# bbot.net
KiCad netlist of a schematic drawn in EAGLE
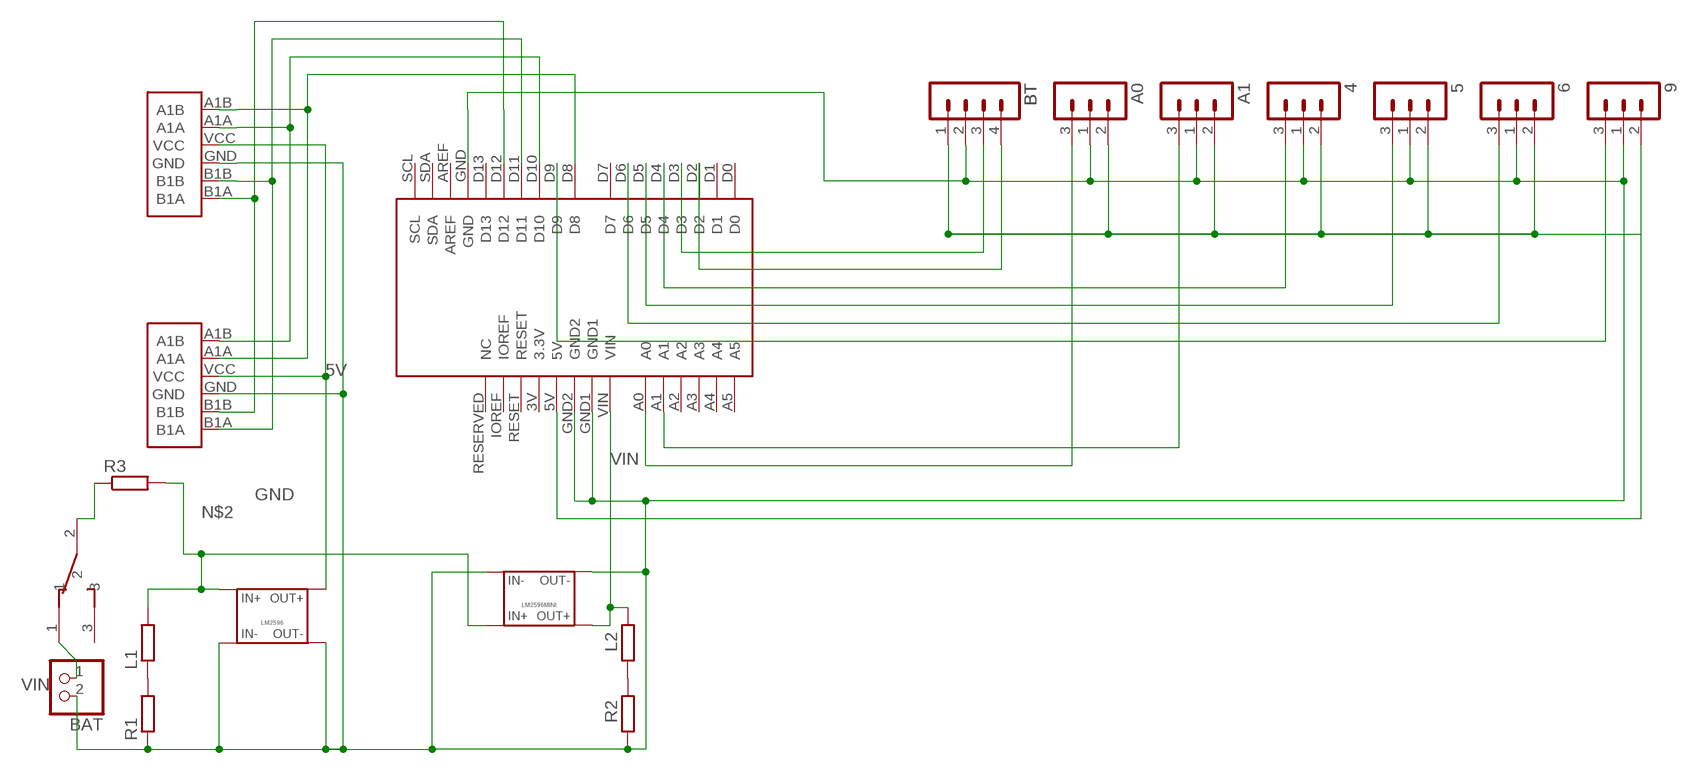
[diagram p0: schematic, sheet 1]

(export (version "E")
  (design (tool "Eeschema 10.0.6"))
  (components
    (comp (ref "4")
      (value "BB-PIN3")
      (footprint "eagle-import:BB-PIN3")
      (libsource (lib "eagle-import") (part "BB-PIN3"))
    )
    (comp (ref "5")
      (value "BB-PIN3")
      (footprint "eagle-import:BB-PIN3")
      (libsource (lib "eagle-import") (part "BB-PIN3"))
    )
    (comp (ref "6")
      (value "BB-PIN3")
      (footprint "eagle-import:BB-PIN3")
      (libsource (lib "eagle-import") (part "BB-PIN3"))
    )
    (comp (ref "9")
      (value "BB-PIN3")
      (footprint "eagle-import:BB-PIN3")
      (libsource (lib "eagle-import") (part "BB-PIN3"))
    )
    (comp (ref "A0")
      (value "BB-PIN3")
      (footprint "eagle-import:BB-PIN3")
      (libsource (lib "eagle-import") (part "BB-PIN3"))
    )
    (comp (ref "A1")
      (value "BB-PIN3")
      (footprint "eagle-import:BB-PIN3")
      (libsource (lib "eagle-import") (part "BB-PIN3"))
    )
    (comp (ref "BAT")
      (value "VIN")
      (footprint "eagle-import:JST-PH-2-THM")
      (libsource (lib "eagle-import") (part "JST_2PIN-THM"))
    )
    (comp (ref "BT")
      (value "BB-HC06")
      (footprint "eagle-import:BB-HC06")
      (libsource (lib "eagle-import") (part "BB-HC06"))
    )
    (comp (ref "L1")
      (value "BB-RESM0805")
      (footprint "eagle-import:M0805")
      (libsource (lib "eagle-import") (part "BB-RESM0805"))
    )
    (comp (ref "L2")
      (value "BB-RESM0805")
      (footprint "eagle-import:M0805")
      (libsource (lib "eagle-import") (part "BB-RESM0805"))
    )
    (comp (ref "LM2596")
      (value "BB-LM2596")
      (footprint "eagle-import:BB-LM2596")
      (fields (field (name "SIZE") "LM2596"))
      (libsource (lib "eagle-import") (part "BB-LM2596"))
    )
    (comp (ref "LM2596MINI")
      (value "BB-LM2596MINI")
      (footprint "eagle-import:BB-LM2596MINI")
      (libsource (lib "eagle-import") (part "BB-LM2596MINI"))
    )
    (comp (ref "R1")
      (value "BB-RESM0805")
      (footprint "eagle-import:M0805")
      (libsource (lib "eagle-import") (part "BB-RESM0805"))
    )
    (comp (ref "R2")
      (value "BB-RESM0805")
      (footprint "eagle-import:M0805")
      (libsource (lib "eagle-import") (part "BB-RESM0805"))
    )
    (comp (ref "R3")
      (value "R-EU_0207/5V")
      (footprint "eagle-import:0207_5V")
      (libsource (lib "eagle-import") (part "R-EU_0207/5V"))
    )
    (comp (ref "SW1")
      (value "BB-SWITCHBB-SW")
      (footprint "eagle-import:BB-SWITCH")
      (libsource (lib "eagle-import") (part "BB-SWITCHBB-SW"))
    )
    (comp (ref "U$1")
      (value "BB-ARD")
      (footprint "eagle-import:BB-ARD")
      (libsource (lib "eagle-import") (part "BB-ARD"))
    )
    (comp (ref "U$2")
      (value "BB-PTEH")
      (footprint "eagle-import:BB-PTEH")
      (libsource (lib "eagle-import") (part "BB-PTEH"))
    )
    (comp (ref "U$3")
      (value "BB-PTEH")
      (footprint "eagle-import:BB-PTEH")
      (libsource (lib "eagle-import") (part "BB-PTEH"))
    )
  )
  (nets
    (net (code "1") (name "/5V") (class "Default")
      (node (ref "LM2596") (pin "OUT+") (pinfunction "OUT+_OUT+") (pintype "bidirectional"))
      (node (ref "U$2") (pin "VCC") (pinfunction "VCC_VCC") (pintype "bidirectional"))
      (node (ref "U$3") (pin "VCC") (pinfunction "VCC_VCC") (pintype "bidirectional"))
    )
    (net (code "2") (name "/GND") (class "Default")
      (node (ref "4") (pin "1") (pinfunction "GND_1") (pintype "passive"))
      (node (ref "5") (pin "1") (pinfunction "GND_1") (pintype "passive"))
      (node (ref "6") (pin "1") (pinfunction "GND_1") (pintype "passive"))
      (node (ref "9") (pin "1") (pinfunction "GND_1") (pintype "passive"))
      (node (ref "A0") (pin "1") (pinfunction "GND_1") (pintype "passive"))
      (node (ref "A1") (pin "1") (pinfunction "GND_1") (pintype "passive"))
      (node (ref "BAT") (pin "2") (pinfunction "1_2") (pintype "passive"))
      (node (ref "BT") (pin "2") (pinfunction "2_2") (pintype "passive"))
      (node (ref "LM2596") (pin "IN-") (pinfunction "IN-_IN-") (pintype "bidirectional"))
      (node (ref "LM2596") (pin "OUT-") (pinfunction "OUT-_OUT-") (pintype "bidirectional"))
      (node (ref "LM2596MINI") (pin "IN-") (pinfunction "IN-_IN-") (pintype "bidirectional"))
      (node (ref "LM2596MINI") (pin "OUT-") (pinfunction "OUT-_OUT-") (pintype "bidirectional"))
      (node (ref "R1") (pin "1") (pinfunction "1_1") (pintype "passive"))
      (node (ref "R2") (pin "1") (pinfunction "1_1") (pintype "passive"))
      (node (ref "U$1") (pin "GND") (pinfunction "GND_GND") (pintype "bidirectional"))
      (node (ref "U$1") (pin "GND1") (pinfunction "GND1_GND1") (pintype "bidirectional"))
      (node (ref "U$1") (pin "GND2") (pinfunction "GND2_GND2") (pintype "bidirectional"))
      (node (ref "U$2") (pin "GND") (pinfunction "GND_GND") (pintype "bidirectional"))
      (node (ref "U$3") (pin "GND") (pinfunction "GND_GND") (pintype "bidirectional"))
    )
    (net (code "3") (name "/N$2") (class "Default")
      (node (ref "R3") (pin "1") (pinfunction "1_1") (pintype "passive"))
      (node (ref "SW1") (pin "2") (pinfunction "2_2") (pintype "bidirectional"))
    )
    (net (code "4") (name "/VIN") (class "Default")
      (node (ref "L2") (pin "2") (pinfunction "2_2") (pintype "passive"))
      (node (ref "LM2596MINI") (pin "OUT+") (pinfunction "OUT+_OUT+") (pintype "bidirectional"))
      (node (ref "U$1") (pin "VIN") (pinfunction "VIN_VIN") (pintype "bidirectional"))
    )
    (net (code "5") (name "Net-(4-5V)") (class "Default")
      (node (ref "4") (pin "2") (pinfunction "5V_2") (pintype "passive"))
      (node (ref "5") (pin "2") (pinfunction "5V_2") (pintype "passive"))
      (node (ref "6") (pin "2") (pinfunction "5V_2") (pintype "passive"))
      (node (ref "9") (pin "2") (pinfunction "5V_2") (pintype "passive"))
      (node (ref "A0") (pin "2") (pinfunction "5V_2") (pintype "passive"))
      (node (ref "A1") (pin "2") (pinfunction "5V_2") (pintype "passive"))
      (node (ref "BT") (pin "1") (pinfunction "1_1") (pintype "passive"))
      (node (ref "U$1") (pin "5V") (pinfunction "5V_5V") (pintype "bidirectional"))
    )
    (net (code "6") (name "Net-(4-S)") (class "Default")
      (node (ref "4") (pin "3") (pinfunction "S_3") (pintype "passive"))
      (node (ref "U$1") (pin "D4") (pinfunction "D4_D4") (pintype "bidirectional"))
    )
    (net (code "7") (name "Net-(5-S)") (class "Default")
      (node (ref "5") (pin "3") (pinfunction "S_3") (pintype "passive"))
      (node (ref "U$1") (pin "D5") (pinfunction "D5_D5") (pintype "bidirectional"))
    )
    (net (code "8") (name "Net-(6-S)") (class "Default")
      (node (ref "6") (pin "3") (pinfunction "S_3") (pintype "passive"))
      (node (ref "U$1") (pin "D6") (pinfunction "D6_D6") (pintype "bidirectional"))
    )
    (net (code "9") (name "Net-(9-S)") (class "Default")
      (node (ref "9") (pin "3") (pinfunction "S_3") (pintype "passive"))
      (node (ref "U$1") (pin "D9") (pinfunction "D9_D9") (pintype "bidirectional"))
    )
    (net (code "10") (name "Net-(A0-S)") (class "Default")
      (node (ref "A0") (pin "3") (pinfunction "S_3") (pintype "passive"))
      (node (ref "U$1") (pin "A0") (pinfunction "A0_A0") (pintype "bidirectional"))
    )
    (net (code "11") (name "Net-(A1-S)") (class "Default")
      (node (ref "A1") (pin "3") (pinfunction "S_3") (pintype "passive"))
      (node (ref "U$1") (pin "A1") (pinfunction "A1_A1") (pintype "bidirectional"))
    )
    (net (code "12") (name "Net-(BAT-2)") (class "Default")
      (node (ref "BAT") (pin "1") (pinfunction "2_1") (pintype "passive"))
      (node (ref "SW1") (pin "1") (pinfunction "1_1") (pintype "bidirectional"))
    )
    (net (code "13") (name "Net-(BT-Pad3)") (class "Default")
      (node (ref "BT") (pin "3") (pinfunction "3_3") (pintype "passive"))
      (node (ref "U$1") (pin "D3") (pinfunction "D3_D3") (pintype "bidirectional"))
    )
    (net (code "14") (name "Net-(BT-Pad4)") (class "Default")
      (node (ref "BT") (pin "4") (pinfunction "4_4") (pintype "passive"))
      (node (ref "U$1") (pin "D2") (pinfunction "D2_D2") (pintype "bidirectional"))
    )
    (net (code "15") (name "Net-(L1-Pad1)") (class "Default")
      (node (ref "L1") (pin "1") (pinfunction "1_1") (pintype "passive"))
      (node (ref "R1") (pin "2") (pinfunction "2_2") (pintype "passive"))
    )
    (net (code "16") (name "Net-(L1-Pad2)") (class "Default")
      (node (ref "L1") (pin "2") (pinfunction "2_2") (pintype "passive"))
      (node (ref "LM2596") (pin "IN+") (pinfunction "IN+_IN+") (pintype "bidirectional"))
      (node (ref "LM2596MINI") (pin "IN+") (pinfunction "IN+_IN+") (pintype "bidirectional"))
      (node (ref "R3") (pin "2") (pinfunction "2_2") (pintype "passive"))
    )
    (net (code "17") (name "Net-(L2-Pad1)") (class "Default")
      (node (ref "L2") (pin "1") (pinfunction "1_1") (pintype "passive"))
      (node (ref "R2") (pin "2") (pinfunction "2_2") (pintype "passive"))
    )
    (net (code "18") (name "Net-(U$1-PadD8)") (class "Default")
      (node (ref "U$1") (pin "D8") (pinfunction "D8_D8") (pintype "bidirectional"))
      (node (ref "U$2") (pin "A1B") (pinfunction "A1B_A1B") (pintype "bidirectional"))
      (node (ref "U$3") (pin "A1A") (pinfunction "A1A_A1A") (pintype "bidirectional"))
    )
    (net (code "19") (name "Net-(U$1-PadD10)") (class "Default")
      (node (ref "U$1") (pin "D10") (pinfunction "D10_D10") (pintype "bidirectional"))
      (node (ref "U$2") (pin "A1A") (pinfunction "A1A_A1A") (pintype "bidirectional"))
      (node (ref "U$3") (pin "A1B") (pinfunction "A1B_A1B") (pintype "bidirectional"))
    )
    (net (code "20") (name "Net-(U$1-PadD11)") (class "Default")
      (node (ref "U$1") (pin "D11") (pinfunction "D11_D11") (pintype "bidirectional"))
      (node (ref "U$2") (pin "B1B") (pinfunction "B1B_B1B") (pintype "bidirectional"))
      (node (ref "U$3") (pin "B1A") (pinfunction "B1A_B1A") (pintype "bidirectional"))
    )
    (net (code "21") (name "Net-(U$1-PadD12)") (class "Default")
      (node (ref "U$1") (pin "D12") (pinfunction "D12_D12") (pintype "bidirectional"))
      (node (ref "U$2") (pin "B1A") (pinfunction "B1A_B1A") (pintype "bidirectional"))
      (node (ref "U$3") (pin "B1B") (pinfunction "B1B_B1B") (pintype "bidirectional"))
    )
    (net (code "22") (name "unconnected-(SW1-Pad3)") (class "Default")
      (node (ref "SW1") (pin "3") (pinfunction "3_3") (pintype "bidirectional"))
    )
    (net (code "23") (name "unconnected-(U$1-3.3V-Pad3V)") (class "Default")
      (node (ref "U$1") (pin "3V") (pinfunction "3.3V_3V") (pintype "bidirectional"))
    )
    (net (code "24") (name "unconnected-(U$1-NC-PadRESERVED)") (class "Default")
      (node (ref "U$1") (pin "RESERVED") (pinfunction "NC_RESERVED") (pintype "bidirectional"))
    )
    (net (code "25") (name "unconnected-(U$1-PadA2)") (class "Default")
      (node (ref "U$1") (pin "A2") (pinfunction "A2_A2") (pintype "bidirectional"))
    )
    (net (code "26") (name "unconnected-(U$1-PadA3)") (class "Default")
      (node (ref "U$1") (pin "A3") (pinfunction "A3_A3") (pintype "bidirectional"))
    )
    (net (code "27") (name "unconnected-(U$1-PadA4)") (class "Default")
      (node (ref "U$1") (pin "A4") (pinfunction "A4_A4") (pintype "bidirectional"))
    )
    (net (code "28") (name "unconnected-(U$1-PadA5)") (class "Default")
      (node (ref "U$1") (pin "A5") (pinfunction "A5_A5") (pintype "bidirectional"))
    )
    (net (code "29") (name "unconnected-(U$1-PadAREF)") (class "Default")
      (node (ref "U$1") (pin "AREF") (pinfunction "AREF_AREF") (pintype "bidirectional"))
    )
    (net (code "30") (name "unconnected-(U$1-PadD0)") (class "Default")
      (node (ref "U$1") (pin "D0") (pinfunction "D0_D0") (pintype "bidirectional"))
    )
    (net (code "31") (name "unconnected-(U$1-PadD1)") (class "Default")
      (node (ref "U$1") (pin "D1") (pinfunction "D1_D1") (pintype "bidirectional"))
    )
    (net (code "32") (name "unconnected-(U$1-PadD7)") (class "Default")
      (node (ref "U$1") (pin "D7") (pinfunction "D7_D7") (pintype "bidirectional"))
    )
    (net (code "33") (name "unconnected-(U$1-PadD13)") (class "Default")
      (node (ref "U$1") (pin "D13") (pinfunction "D13_D13") (pintype "bidirectional"))
    )
    (net (code "34") (name "unconnected-(U$1-PadIOREF)") (class "Default")
      (node (ref "U$1") (pin "IOREF") (pinfunction "IOREF_IOREF") (pintype "bidirectional"))
    )
    (net (code "35") (name "unconnected-(U$1-PadRESET)") (class "Default")
      (node (ref "U$1") (pin "RESET") (pinfunction "RESET_RESET") (pintype "bidirectional"))
    )
    (net (code "36") (name "unconnected-(U$1-PadSCL)") (class "Default")
      (node (ref "U$1") (pin "SCL") (pinfunction "SCL_SCL") (pintype "bidirectional"))
    )
    (net (code "37") (name "unconnected-(U$1-PadSDA)") (class "Default")
      (node (ref "U$1") (pin "SDA") (pinfunction "SDA_SDA") (pintype "bidirectional"))
    )
  )
)
